# Main.net
KiCad netlist of a schematic drawn in Altium Designer
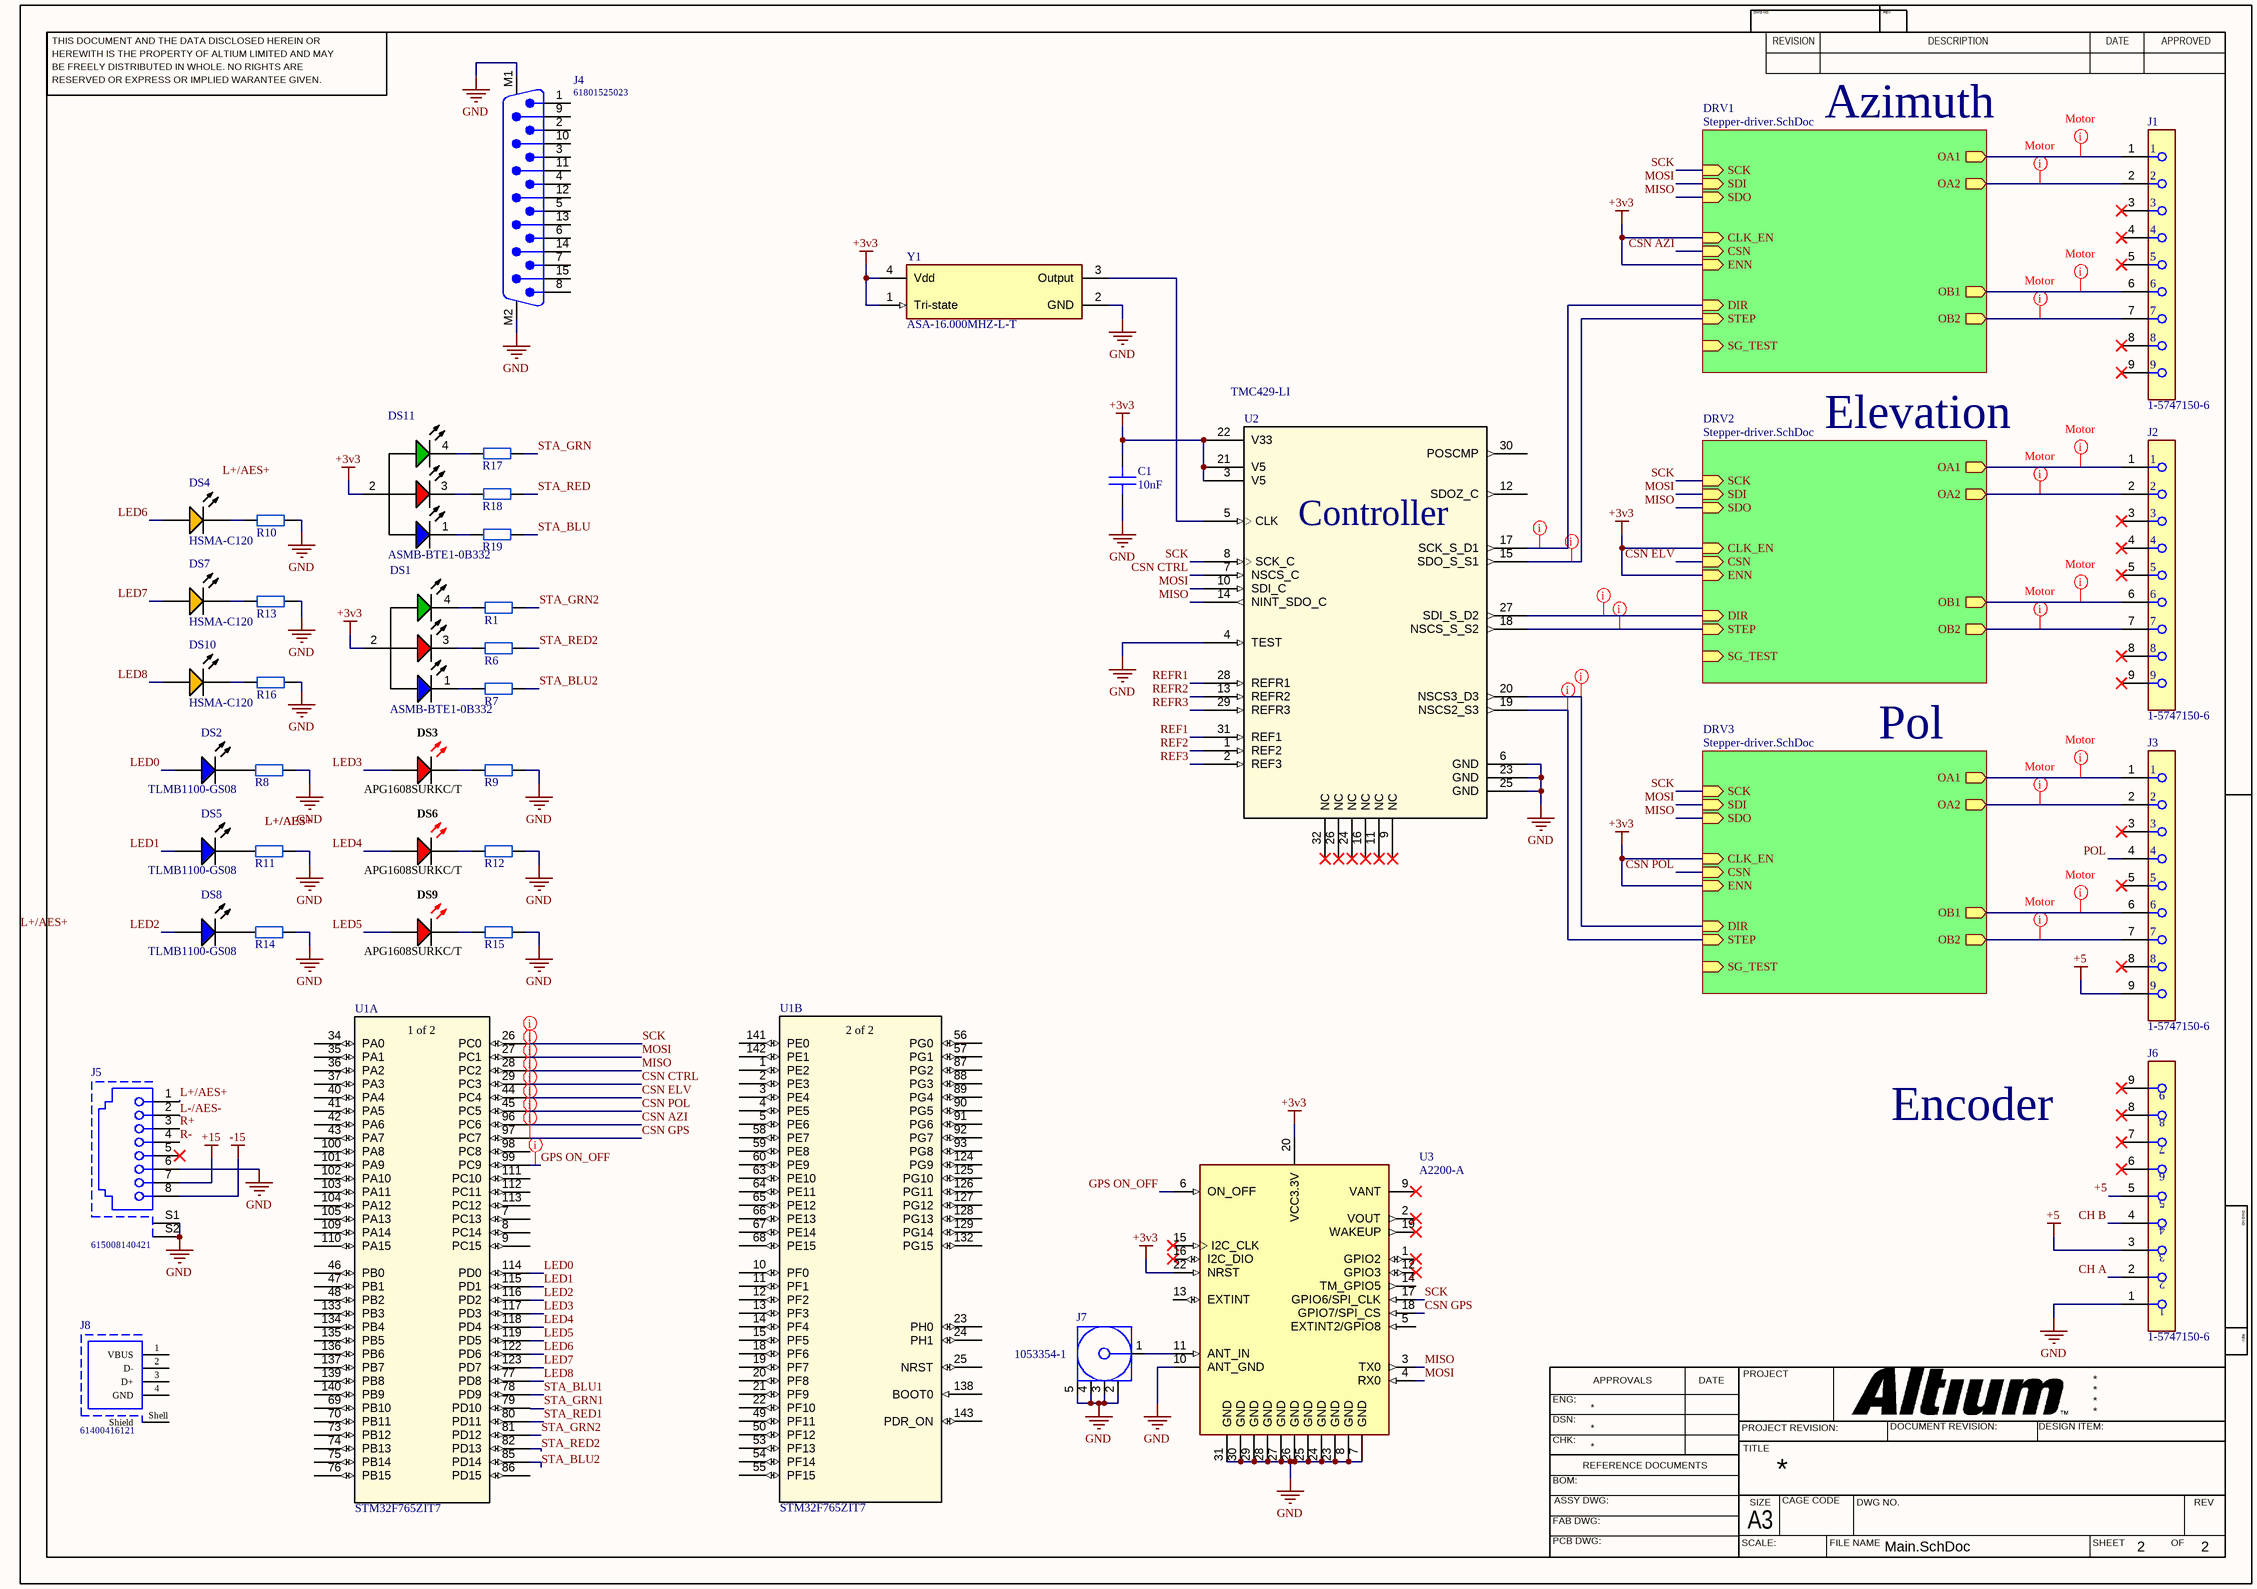
[diagram p0: Main.SchDoc]

(export (version "E")
  (design (tool "Eeschema 10.0.6"))
  (components
    (comp (ref "C1")
      (value "10nF")
      (footprint "C0603 (1608)")
      (fields (field (name "Comment") "Cap SMD"))
      (libsource (lib "Moto Symbol Lib") (part "Cap SMD"))
    )
    (comp (ref "DS1")
      (value "ASMB-BTE1-0B332")
      (footprint "FP-ASMB-BTE1-0B332-MFG")
      (description "LED RGB DIFFUSED 4PLCC SMD")
      (fields
        (field (name "MANUFACTURER") "Broadcom")
        (field (name "OCTOPART") "https://octopart.com/asmb-bte1-0b332-broadcom-71127192")
      )
      (libsource (lib "Moto Symbol Lib") (part "ASMB-BTE1-0B332 RGB LED"))
    )
    (comp (ref "DS2")
      (value "TLMB1100-GS08")
      (footprint "VISH-TLMX1100-2_V")
      (description "Blue LED, 10 mA, 3.9 V, -40 to 100 degC, 2-Pin SMD (0603), RoHS, Tape and Reel")
      (fields (field (name "TOLERANCE") "10%"))
      (libsource (lib "Altium Content Vault") (part "LED-BLUE-AK-2"))
    )
    (comp (ref "DS3")
      (value "APG1608SURKC/T")
      (footprint "KING-LED0603-25-RED_V")
      (fields (field (name "MANUFACTURER") "Kingbright"))
      (libsource (lib "Altium Content Vault") (part "KING-LED_RED_A1K2-2"))
    )
    (comp (ref "DS4")
      (value "HSMA-C120")
      (footprint "AVAG-HSMA-C120-2_V")
      (description "High Performance Chip LED, 1.9 V, -40 to 85 degC, 2-Pin SMD (0603), RoHS, Tape and Reel")
      (fields (field (name "MANUFACTURER") "Avago"))
      (libsource (lib "Altium Content Vault") (part "LED-AMBER-AK-2"))
    )
    (comp (ref "DS5")
      (value "TLMB1100-GS08")
      (footprint "VISH-TLMX1100-2_V")
      (description "Blue LED, 10 mA, 3.9 V, -40 to 100 degC, 2-Pin SMD (0603), RoHS, Tape and Reel")
      (fields (field (name "TOLERANCE") "10%"))
      (libsource (lib "Altium Content Vault") (part "LED-BLUE-AK-2"))
    )
    (comp (ref "DS6")
      (value "APG1608SURKC/T")
      (footprint "KING-LED0603-25-RED_V")
      (fields (field (name "MANUFACTURER") "Kingbright"))
      (libsource (lib "Altium Content Vault") (part "KING-LED_RED_A1K2-2"))
    )
    (comp (ref "DS7")
      (value "HSMA-C120")
      (footprint "AVAG-HSMA-C120-2_V")
      (description "High Performance Chip LED, 1.9 V, -40 to 85 degC, 2-Pin SMD (0603), RoHS, Tape and Reel")
      (fields (field (name "MANUFACTURER") "Avago"))
      (libsource (lib "Altium Content Vault") (part "LED-AMBER-AK-2"))
    )
    (comp (ref "DS8")
      (value "TLMB1100-GS08")
      (footprint "VISH-TLMX1100-2_V")
      (description "Blue LED, 10 mA, 3.9 V, -40 to 100 degC, 2-Pin SMD (0603), RoHS, Tape and Reel")
      (fields (field (name "TOLERANCE") "10%"))
      (libsource (lib "Altium Content Vault") (part "LED-BLUE-AK-2"))
    )
    (comp (ref "DS9")
      (value "APG1608SURKC/T")
      (footprint "KING-LED0603-25-RED_V")
      (fields (field (name "MANUFACTURER") "Kingbright"))
      (libsource (lib "Altium Content Vault") (part "KING-LED_RED_A1K2-2"))
    )
    (comp (ref "DS10")
      (value "HSMA-C120")
      (footprint "AVAG-HSMA-C120-2_V")
      (description "High Performance Chip LED, 1.9 V, -40 to 85 degC, 2-Pin SMD (0603), RoHS, Tape and Reel")
      (fields (field (name "MANUFACTURER") "Avago"))
      (libsource (lib "Altium Content Vault") (part "LED-AMBER-AK-2"))
    )
    (comp (ref "DS11")
      (value "ASMB-BTE1-0B332")
      (footprint "FP-ASMB-BTE1-0B332-MFG")
      (description "LED RGB DIFFUSED 4PLCC SMD")
      (fields
        (field (name "MANUFACTURER") "Broadcom")
        (field (name "OCTOPART") "https://octopart.com/asmb-bte1-0b332-broadcom-71127192")
      )
      (libsource (lib "Moto Symbol Lib") (part "ASMB-BTE1-0B332 RGB LED"))
    )
    (comp (ref "J1")
      (value "1-5747150-6")
      (footprint "FP-1-5747150-6-MFG")
      (description "CONN D-SUB RCPT 9POS VERT SOLDER")
      (fields
        (field (name "OCTOPART") "https://octopart.com/1-5747150-6-te+connectivity-39500344")
        (field (name "MANUFACTURER") "TE Connectivity")
      )
      (libsource (lib "Altium Content Vault") (part "deee9d0d87fff07c08bdfa5b86cd5a5"))
    )
    (comp (ref "J2")
      (value "1-5747150-6")
      (footprint "FP-1-5747150-6-MFG")
      (description "CONN D-SUB RCPT 9POS VERT SOLDER")
      (fields
        (field (name "OCTOPART") "https://octopart.com/1-5747150-6-te+connectivity-39500344")
        (field (name "MANUFACTURER") "TE Connectivity")
      )
      (libsource (lib "Altium Content Vault") (part "deee9d0d87fff07c08bdfa5b86cd5a5"))
    )
    (comp (ref "J3")
      (value "1-5747150-6")
      (footprint "FP-1-5747150-6-MFG")
      (description "CONN D-SUB RCPT 9POS VERT SOLDER")
      (fields
        (field (name "OCTOPART") "https://octopart.com/1-5747150-6-te+connectivity-39500344")
        (field (name "MANUFACTURER") "TE Connectivity")
      )
      (libsource (lib "Altium Content Vault") (part "deee9d0d87fff07c08bdfa5b86cd5a5"))
    )
    (comp (ref "J4")
      (value "61801525023")
      (footprint "61801525023")
      (description "Male PCB Connector WR-DSUB, Vertical, 15 pins")
      (fields (field (name "MANUFACTURER") "Wurth Elektronik") (field (name "PUBLISHER") "WurthElektronik"))
      (libsource (lib "Altium Content Vault") (part "WE-CN-2S-2M-D15"))
    )
    (comp (ref "J5")
      (value "615008140421")
      (footprint "615008140421")
      (description "Modular Jack WR-MJ, Rear Post, Shielded, Vertical Entry, THT, 8P8C")
      (fields (field (name "MANUFACTURER") "Wurth Elektronik") (field (name "PUBLISHER") "WurthElektronik"))
      (libsource (lib "Altium Content Vault") (part "WE-CN-1P-2F-J8"))
    )
    (comp (ref "J6")
      (value "1-5747150-6")
      (footprint "FP-1-5747150-6-MFG")
      (description "CONN D-SUB RCPT 9POS VERT SOLDER")
      (fields
        (field (name "OCTOPART") "https://octopart.com/1-5747150-6-te+connectivity-39500344")
        (field (name "MANUFACTURER") "TE Connectivity")
      )
      (libsource (lib "") (part "deee9d0d87fff07c08bdfa5b86cd5a5_1"))
    )
    (comp (ref "J7")
      (value "1053354-1")
      (footprint "TECO-1053354-1_V")
      (description "Female Coaxial Connector, Pitch 2.55 mm, Height 9.5 mm, Tail Length 3.9 mm, RoHS, Bulk")
      (fields (field (name "MANUFACTURER") "TE Connectivity"))
      (libsource (lib "Altium Content Vault") (part "CN-S-4F-RF5"))
    )
    (comp (ref "J8")
      (value "61400416121")
      (footprint "61400416121")
      (description "USB 2.0 Type B Receptacle WR-COM, Horizontal, THT, with Pads and Pegs")
      (fields (field (name "MANUFACTURER") "Wurth Elektronik") (field (name "PUBLISHER") "WurthElektronik"))
      (libsource (lib "Altium Content Vault") (part "WE-USB-4-1SHLD"))
    )
    (comp (ref "R1")
      (value "Res")
      (footprint "R0603 (1608)")
      (libsource (lib "Moto Symbol Lib") (part "Resistor EU"))
    )
    (comp (ref "R6")
      (value "Res")
      (footprint "R0603 (1608)")
      (libsource (lib "Moto Symbol Lib") (part "Resistor EU"))
    )
    (comp (ref "R7")
      (value "Res")
      (footprint "R0603 (1608)")
      (libsource (lib "Moto Symbol Lib") (part "Resistor EU"))
    )
    (comp (ref "R8")
      (value "Res")
      (footprint "R0603 (1608)")
      (libsource (lib "Moto Symbol Lib") (part "Resistor EU"))
    )
    (comp (ref "R9")
      (value "Res")
      (footprint "R0603 (1608)")
      (libsource (lib "Moto Symbol Lib") (part "Resistor EU"))
    )
    (comp (ref "R10")
      (value "Res")
      (footprint "R0603 (1608)")
      (libsource (lib "Moto Symbol Lib") (part "Resistor EU"))
    )
    (comp (ref "R11")
      (value "Res")
      (footprint "R0603 (1608)")
      (libsource (lib "Moto Symbol Lib") (part "Resistor EU"))
    )
    (comp (ref "R12")
      (value "Res")
      (footprint "R0603 (1608)")
      (libsource (lib "Moto Symbol Lib") (part "Resistor EU"))
    )
    (comp (ref "R13")
      (value "Res")
      (footprint "R0603 (1608)")
      (libsource (lib "Moto Symbol Lib") (part "Resistor EU"))
    )
    (comp (ref "R14")
      (value "Res")
      (footprint "R0603 (1608)")
      (libsource (lib "Moto Symbol Lib") (part "Resistor EU"))
    )
    (comp (ref "R15")
      (value "Res")
      (footprint "R0603 (1608)")
      (libsource (lib "Moto Symbol Lib") (part "Resistor EU"))
    )
    (comp (ref "R16")
      (value "Res")
      (footprint "R0603 (1608)")
      (libsource (lib "Moto Symbol Lib") (part "Resistor EU"))
    )
    (comp (ref "R17")
      (value "Res")
      (footprint "R0603 (1608)")
      (libsource (lib "Moto Symbol Lib") (part "Resistor EU"))
    )
    (comp (ref "R18")
      (value "Res")
      (footprint "R0603 (1608)")
      (libsource (lib "Moto Symbol Lib") (part "Resistor EU"))
    )
    (comp (ref "R19")
      (value "Res")
      (footprint "R0603 (1608)")
      (libsource (lib "Moto Symbol Lib") (part "Resistor EU"))
    )
    (comp (ref "U1")
      (value "STM32F765ZIT7")
      (footprint "LQFP-144_STM-M")
      (description "No Description Available")
      (fields (field (name "COPYRIGHT") "Copyright (C) 2018 Accelerated Designs. All rights reserved"))
      (libsource (lib "Moto Symbol Lib") (part "STM32F765ZIT7"))
    )
    (comp (ref "U2")
      (value "TMC429-LI")
      (footprint "QFN32_5X5_TRI-M")
      (description "No Description Available")
      (fields (field (name "COPYRIGHT") "Copyright (C) 2016 Accelerated Designs. All rights reserved"))
      (libsource (lib "Moto Symbol Lib") (part "TMC429-LI"))
    )
    (comp (ref "U3")
      (value "A2200-A")
      (footprint "SnapEDApcb:XCVR_A2200-A")
      (description "SiRFstarIVâ„¢ RF Receiver GPS 1.575GHz -163dBm 115.2kbps Module")
      (fields (field (name "MF") "Maestro Wireless"))
      (libsource (lib "Moto Symbol Lib") (part "A2200-A"))
    )
    (comp (ref "Y1")
      (value "ASA-16.000MHZ-L-T")
      (footprint "FP-ASA-MFG")
      (description "XTAL OSC XO 16.0000MHZ HCMOS SMD")
      (fields
        (field (name "OCTOPART") "https://octopart.com/asa-16.000mhz-l-t-abracon-21707822")
        (field (name "MANUFACTURER") "Abracon")
      )
      (libsource (lib "Altium Content Vault") (part "7c953fa1d91b086b7cda9813af2bec8"))
    )
  )
  (nets
    (net (code "1") (name "+3v3") (class "Default")
      (node (ref "C1") (pin "2") (pinfunction "2_2") (pintype "power_in"))
      (node (ref "DS1") (pin "2") (pinfunction "Common_Anode_2") (pintype "passive"))
      (node (ref "DS11") (pin "2") (pinfunction "Common_Anode_2") (pintype "passive"))
      (node (ref "U2") (pin "21") (pinfunction "V5_21") (pintype "power_in"))
      (node (ref "U2") (pin "22") (pinfunction "V33_22") (pintype "power_in"))
      (node (ref "U2") (pin "3") (pinfunction "V5_3") (pintype "power_in"))
      (node (ref "U3") (pin "20") (pinfunction "VCC3.3V_20") (pintype "power_in"))
      (node (ref "U3") (pin "22") (pinfunction "NRST_22") (pintype "input"))
      (node (ref "Y1") (pin "1") (pinfunction "Tri-state_1") (pintype "input"))
      (node (ref "Y1") (pin "4") (pinfunction "Vdd_4") (pintype "power_in"))
    )
    (net (code "2") (name "+5") (class "Default")
      (node (ref "J3") (pin "9") (pinfunction "9_9") (pintype "passive"))
      (node (ref "J6") (pin "3") (pinfunction "3_3") (pintype "passive"))
      (node (ref "J6") (pin "5") (pinfunction "5_5") (pintype "passive"))
    )
    (net (code "3") (name "+15") (class "Default")
      (node (ref "J5") (pin "7") (pinfunction "7_7") (pintype "passive"))
    )
    (net (code "4") (name "-15") (class "Default")
      (node (ref "J5") (pin "8") (pinfunction "8_8") (pintype "passive"))
    )
    (net (code "5") (name "/<NO NET>") (class "Default")
      (node (ref "U2") (pin "19") (pinfunction "NSCS2_S3_19") (pintype "output"))
    )
    (net (code "6") (name "/CH A") (class "Default")
      (node (ref "J6") (pin "2") (pinfunction "2_2") (pintype "passive"))
    )
    (net (code "7") (name "/CH B") (class "Default")
      (node (ref "J6") (pin "4") (pinfunction "4_4") (pintype "passive"))
    )
    (net (code "8") (name "/CSN AZI") (class "Default")
      (node (ref "U1") (pin "96") (pinfunction "PC6_96") (pintype "bidirectional"))
    )
    (net (code "9") (name "/CSN CTRL") (class "Default")
      (node (ref "U1") (pin "29") (pinfunction "PC3_29") (pintype "bidirectional"))
      (node (ref "U2") (pin "7") (pinfunction "NSCS_C_7") (pintype "input"))
    )
    (net (code "10") (name "/CSN ELV") (class "Default")
      (node (ref "U1") (pin "44") (pinfunction "PC4_44") (pintype "bidirectional"))
    )
    (net (code "11") (name "/CSN GPS") (class "Default")
      (node (ref "U1") (pin "97") (pinfunction "PC7_97") (pintype "bidirectional"))
      (node (ref "U3") (pin "18") (pinfunction "GPIO7/SPI_CS_18") (pintype "input"))
    )
    (net (code "12") (name "/CSN POL") (class "Default")
      (node (ref "U1") (pin "45") (pinfunction "PC5_45") (pintype "bidirectional"))
    )
    (net (code "13") (name "/DIR") (class "Default")
      (node (ref "U2") (pin "20") (pinfunction "NSCS3_D3_20") (pintype "output"))
    )
    (net (code "14") (name "/DIR_1") (class "Default")
      (node (ref "U2") (pin "17") (pinfunction "SCK_S_D1_17") (pintype "output"))
    )
    (net (code "15") (name "/DIR_2") (class "Default")
      (node (ref "U2") (pin "27") (pinfunction "SDI_S_D2_27") (pintype "output"))
    )
    (net (code "16") (name "/GPS ON_OFF") (class "Default")
      (node (ref "U1") (pin "99") (pinfunction "PC9_99") (pintype "bidirectional"))
      (node (ref "U3") (pin "6") (pinfunction "ON_OFF_6") (pintype "input"))
    )
    (net (code "17") (name "/L+{slash}AES+") (class "Default")
      (node (ref "J5") (pin "1") (pinfunction "1_1") (pintype "passive"))
    )
    (net (code "18") (name "/L-{slash}AES-") (class "Default")
      (node (ref "J5") (pin "2") (pinfunction "2_2") (pintype "passive"))
    )
    (net (code "19") (name "/LED0") (class "Default")
      (node (ref "DS2") (pin "1") (pinfunction "A_1") (pintype "passive"))
      (node (ref "U1") (pin "114") (pinfunction "PD0_114") (pintype "bidirectional"))
    )
    (net (code "20") (name "/LED1") (class "Default")
      (node (ref "DS5") (pin "1") (pinfunction "A_1") (pintype "passive"))
      (node (ref "U1") (pin "115") (pinfunction "PD1_115") (pintype "bidirectional"))
    )
    (net (code "21") (name "/LED2") (class "Default")
      (node (ref "DS8") (pin "1") (pinfunction "A_1") (pintype "passive"))
      (node (ref "U1") (pin "116") (pinfunction "PD2_116") (pintype "bidirectional"))
    )
    (net (code "22") (name "/LED3") (class "Default")
      (node (ref "DS3") (pin "1") (pinfunction "A_1") (pintype "passive"))
      (node (ref "U1") (pin "117") (pinfunction "PD3_117") (pintype "bidirectional"))
    )
    (net (code "23") (name "/LED4") (class "Default")
      (node (ref "DS6") (pin "1") (pinfunction "A_1") (pintype "passive"))
      (node (ref "U1") (pin "118") (pinfunction "PD4_118") (pintype "bidirectional"))
    )
    (net (code "24") (name "/LED5") (class "Default")
      (node (ref "DS9") (pin "1") (pinfunction "A_1") (pintype "passive"))
      (node (ref "U1") (pin "119") (pinfunction "PD5_119") (pintype "bidirectional"))
    )
    (net (code "25") (name "/LED6") (class "Default")
      (node (ref "DS4") (pin "1") (pinfunction "A_1") (pintype "passive"))
      (node (ref "U1") (pin "122") (pinfunction "PD6_122") (pintype "bidirectional"))
    )
    (net (code "26") (name "/LED7") (class "Default")
      (node (ref "DS7") (pin "1") (pinfunction "A_1") (pintype "passive"))
      (node (ref "U1") (pin "123") (pinfunction "PD7_123") (pintype "bidirectional"))
    )
    (net (code "27") (name "/LED8") (class "Default")
      (node (ref "DS10") (pin "1") (pinfunction "A_1") (pintype "passive"))
      (node (ref "U1") (pin "77") (pinfunction "PD8_77") (pintype "bidirectional"))
    )
    (net (code "28") (name "/MISO") (class "Default")
      (node (ref "U1") (pin "28") (pinfunction "PC2_28") (pintype "bidirectional"))
      (node (ref "U2") (pin "14") (pinfunction "NINT_SDO_C_14") (pintype "output"))
      (node (ref "U3") (pin "3") (pinfunction "TX0_3") (pintype "output"))
    )
    (net (code "29") (name "/MOSI") (class "Default")
      (node (ref "U1") (pin "27") (pinfunction "PC1_27") (pintype "bidirectional"))
      (node (ref "U2") (pin "10") (pinfunction "SDI_C_10") (pintype "input"))
      (node (ref "U3") (pin "4") (pinfunction "RX0_4") (pintype "input"))
    )
    (net (code "30") (name "/OA1") (class "Default")
      (node (ref "J3") (pin "1") (pinfunction "1_1") (pintype "passive"))
    )
    (net (code "31") (name "/OA1_1") (class "Default")
      (node (ref "J1") (pin "1") (pinfunction "1_1") (pintype "passive"))
    )
    (net (code "32") (name "/OA1_2") (class "Default")
      (node (ref "J2") (pin "1") (pinfunction "1_1") (pintype "passive"))
    )
    (net (code "33") (name "/OA2") (class "Default")
      (node (ref "J3") (pin "2") (pinfunction "2_2") (pintype "passive"))
    )
    (net (code "34") (name "/OA2_1") (class "Default")
      (node (ref "J1") (pin "2") (pinfunction "2_2") (pintype "passive"))
    )
    (net (code "35") (name "/OA2_2") (class "Default")
      (node (ref "J2") (pin "2") (pinfunction "2_2") (pintype "passive"))
    )
    (net (code "36") (name "/OB1") (class "Default")
      (node (ref "J3") (pin "6") (pinfunction "6_6") (pintype "passive"))
    )
    (net (code "37") (name "/OB1_1") (class "Default")
      (node (ref "J1") (pin "6") (pinfunction "6_6") (pintype "passive"))
    )
    (net (code "38") (name "/OB1_2") (class "Default")
      (node (ref "J2") (pin "6") (pinfunction "6_6") (pintype "passive"))
    )
    (net (code "39") (name "/OB2") (class "Default")
      (node (ref "J3") (pin "7") (pinfunction "7_7") (pintype "passive"))
    )
    (net (code "40") (name "/OB2_1") (class "Default")
      (node (ref "J1") (pin "7") (pinfunction "7_7") (pintype "passive"))
    )
    (net (code "41") (name "/OB2_2") (class "Default")
      (node (ref "J2") (pin "7") (pinfunction "7_7") (pintype "passive"))
    )
    (net (code "42") (name "/POL") (class "Default")
      (node (ref "J3") (pin "4") (pinfunction "4_4") (pintype "passive"))
    )
    (net (code "43") (name "/R+") (class "Default")
      (node (ref "J5") (pin "3") (pinfunction "3_3") (pintype "passive"))
    )
    (net (code "44") (name "/R-") (class "Default")
      (node (ref "J5") (pin "4") (pinfunction "4_4") (pintype "passive"))
    )
    (net (code "45") (name "/REF1") (class "Default")
      (node (ref "U2") (pin "31") (pinfunction "REF1_31") (pintype "input"))
    )
    (net (code "46") (name "/REF2") (class "Default")
      (node (ref "U2") (pin "1") (pinfunction "REF2_1") (pintype "input"))
    )
    (net (code "47") (name "/REF3") (class "Default")
      (node (ref "U2") (pin "2") (pinfunction "REF3_2") (pintype "input"))
    )
    (net (code "48") (name "/REFR1") (class "Default")
      (node (ref "U2") (pin "28") (pinfunction "REFR1_28") (pintype "input"))
    )
    (net (code "49") (name "/REFR2") (class "Default")
      (node (ref "U2") (pin "13") (pinfunction "REFR2_13") (pintype "input"))
    )
    (net (code "50") (name "/REFR3") (class "Default")
      (node (ref "U2") (pin "29") (pinfunction "REFR3_29") (pintype "input"))
    )
    (net (code "51") (name "/SCK") (class "Default")
      (node (ref "U1") (pin "26") (pinfunction "PC0_26") (pintype "bidirectional"))
      (node (ref "U2") (pin "8") (pinfunction "SCK_C_8") (pintype "input"))
      (node (ref "U3") (pin "17") (pinfunction "GPIO6/SPI_CLK_17") (pintype "input"))
    )
    (net (code "55") (name "/STA_BLU") (class "Default")
      (node (ref "R19") (pin "2") (pinfunction "2_2") (pintype "power_in"))
    )
    (net (code "56") (name "/STA_BLU1") (class "Default")
      (node (ref "U1") (pin "78") (pinfunction "PD9_78") (pintype "bidirectional"))
    )
    (net (code "57") (name "/STA_BLU2") (class "Default")
      (node (ref "R7") (pin "2") (pinfunction "2_2") (pintype "power_in"))
      (node (ref "U1") (pin "85") (pinfunction "PD14_85") (pintype "bidirectional"))
    )
    (net (code "58") (name "/STA_GRN") (class "Default")
      (node (ref "R17") (pin "2") (pinfunction "2_2") (pintype "power_in"))
    )
    (net (code "60") (name "/STA_GRN2") (class "Default")
      (node (ref "R1") (pin "2") (pinfunction "2_2") (pintype "power_in"))
      (node (ref "U1") (pin "81") (pinfunction "PD12_81") (pintype "bidirectional"))
    )
    (net (code "61") (name "/STA_RED") (class "Default")
      (node (ref "R18") (pin "2") (pinfunction "2_2") (pintype "power_in"))
    )
    (net (code "62") (name "/STA_RED1") (class "Default")
      (node (ref "U1") (pin "80") (pinfunction "PD11_80") (pintype "bidirectional"))
    )
    (net (code "63") (name "/STA_RED2") (class "Default")
      (node (ref "R6") (pin "2") (pinfunction "2_2") (pintype "power_in"))
      (node (ref "U1") (pin "82") (pinfunction "PD13_82") (pintype "bidirectional"))
    )
    (net (code "64") (name "/STEP") (class "Default")
      (node (ref "U2") (pin "18") (pinfunction "NSCS_S_S2_18") (pintype "output"))
    )
    (net (code "65") (name "/STEP_1") (class "Default")
      (node (ref "U2") (pin "15") (pinfunction "SDO_S_S1_15") (pintype "output"))
    )
    (net (code "66") (name "GND") (class "Default")
      (node (ref "C1") (pin "1") (pinfunction "1_1") (pintype "power_in"))
      (node (ref "J4") (pin "M1") (pinfunction "M1_M1") (pintype "passive"))
      (node (ref "J4") (pin "M2") (pinfunction "M2_M2") (pintype "passive"))
      (node (ref "J5") (pin "6") (pinfunction "6_6") (pintype "passive"))
      (node (ref "J5") (pin "S1") (pinfunction "S1_S1") (pintype "passive"))
      (node (ref "J5") (pin "S2") (pinfunction "S2_S2") (pintype "passive"))
      (node (ref "J6") (pin "1") (pinfunction "1_1") (pintype "passive"))
      (node (ref "J7") (pin "2") (pinfunction "2_2") (pintype "passive"))
      (node (ref "J7") (pin "3") (pinfunction "3_3") (pintype "passive"))
      (node (ref "J7") (pin "4") (pinfunction "4_4") (pintype "passive"))
      (node (ref "J7") (pin "5") (pinfunction "5_5") (pintype "passive"))
      (node (ref "R10") (pin "2") (pinfunction "2_2") (pintype "power_in"))
      (node (ref "R11") (pin "2") (pinfunction "2_2") (pintype "power_in"))
      (node (ref "R12") (pin "2") (pinfunction "2_2") (pintype "power_in"))
      (node (ref "R13") (pin "2") (pinfunction "2_2") (pintype "power_in"))
      (node (ref "R14") (pin "2") (pinfunction "2_2") (pintype "power_in"))
      (node (ref "R15") (pin "2") (pinfunction "2_2") (pintype "power_in"))
      (node (ref "R16") (pin "2") (pinfunction "2_2") (pintype "power_in"))
      (node (ref "R8") (pin "2") (pinfunction "2_2") (pintype "power_in"))
      (node (ref "R9") (pin "2") (pinfunction "2_2") (pintype "power_in"))
      (node (ref "U2") (pin "23") (pinfunction "GND_23") (pintype "power_in"))
      (node (ref "U2") (pin "25") (pinfunction "GND_25") (pintype "power_in"))
      (node (ref "U2") (pin "4") (pinfunction "TEST_4") (pintype "input"))
      (node (ref "U2") (pin "6") (pinfunction "GND_6") (pintype "power_in"))
      (node (ref "U3") (pin "10") (pinfunction "ANT_GND_10") (pintype "power_in"))
      (node (ref "U3") (pin "23") (pinfunction "GND_23") (pintype "power_in"))
      (node (ref "U3") (pin "24") (pinfunction "GND_24") (pintype "power_in"))
      (node (ref "U3") (pin "25") (pinfunction "GND_25") (pintype "power_in"))
      (node (ref "U3") (pin "26") (pinfunction "GND_26") (pintype "power_in"))
      (node (ref "U3") (pin "27") (pinfunction "GND_27") (pintype "power_in"))
      (node (ref "U3") (pin "28") (pinfunction "GND_28") (pintype "power_in"))
      (node (ref "U3") (pin "29") (pinfunction "GND_29") (pintype "power_in"))
      (node (ref "U3") (pin "30") (pinfunction "GND_30") (pintype "power_in"))
      (node (ref "U3") (pin "31") (pinfunction "GND_31") (pintype "power_in"))
      (node (ref "U3") (pin "7") (pinfunction "GND_7") (pintype "power_in"))
      (node (ref "U3") (pin "8") (pinfunction "GND_8") (pintype "power_in"))
      (node (ref "Y1") (pin "2") (pinfunction "GND_2") (pintype "power_in"))
    )
    (net (code "67") (name "Net-(DS1-Cathode(Blue))") (class "Default")
      (node (ref "DS1") (pin "1") (pinfunction "Cathode(Blue)_1") (pintype "passive"))
      (node (ref "R7") (pin "1") (pinfunction "1_1") (pintype "power_in"))
    )
    (net (code "68") (name "Net-(DS1-Cathode(Green))") (class "Default")
      (node (ref "DS1") (pin "4") (pinfunction "Cathode(Green)_4") (pintype "passive"))
      (node (ref "R1") (pin "1") (pinfunction "1_1") (pintype "power_in"))
    )
    (net (code "69") (name "Net-(DS1-Cathode(Red))") (class "Default")
      (node (ref "DS1") (pin "3") (pinfunction "Cathode(Red)_3") (pintype "passive"))
      (node (ref "R6") (pin "1") (pinfunction "1_1") (pintype "power_in"))
    )
    (net (code "70") (name "Net-(DS2-K)") (class "Default")
      (node (ref "DS2") (pin "2") (pinfunction "K_2") (pintype "passive"))
      (node (ref "R8") (pin "1") (pinfunction "1_1") (pintype "power_in"))
    )
    (net (code "71") (name "Net-(DS3-K)") (class "Default")
      (node (ref "DS3") (pin "2") (pinfunction "K_2") (pintype "passive"))
      (node (ref "R9") (pin "1") (pinfunction "1_1") (pintype "power_in"))
    )
    (net (code "72") (name "Net-(DS4-K)") (class "Default")
      (node (ref "DS4") (pin "2") (pinfunction "K_2") (pintype "passive"))
      (node (ref "R10") (pin "1") (pinfunction "1_1") (pintype "power_in"))
    )
    (net (code "73") (name "Net-(DS5-K)") (class "Default")
      (node (ref "DS5") (pin "2") (pinfunction "K_2") (pintype "passive"))
      (node (ref "R11") (pin "1") (pinfunction "1_1") (pintype "power_in"))
    )
    (net (code "74") (name "Net-(DS6-K)") (class "Default")
      (node (ref "DS6") (pin "2") (pinfunction "K_2") (pintype "passive"))
      (node (ref "R12") (pin "1") (pinfunction "1_1") (pintype "power_in"))
    )
    (net (code "75") (name "Net-(DS7-K)") (class "Default")
      (node (ref "DS7") (pin "2") (pinfunction "K_2") (pintype "passive"))
      (node (ref "R13") (pin "1") (pinfunction "1_1") (pintype "power_in"))
    )
    (net (code "76") (name "Net-(DS8-K)") (class "Default")
      (node (ref "DS8") (pin "2") (pinfunction "K_2") (pintype "passive"))
      (node (ref "R14") (pin "1") (pinfunction "1_1") (pintype "power_in"))
    )
    (net (code "77") (name "Net-(DS9-K)") (class "Default")
      (node (ref "DS9") (pin "2") (pinfunction "K_2") (pintype "passive"))
      (node (ref "R15") (pin "1") (pinfunction "1_1") (pintype "power_in"))
    )
    (net (code "78") (name "Net-(DS10-K)") (class "Default")
      (node (ref "DS10") (pin "2") (pinfunction "K_2") (pintype "passive"))
      (node (ref "R16") (pin "1") (pinfunction "1_1") (pintype "power_in"))
    )
    (net (code "79") (name "Net-(DS11-Cathode(Blue))") (class "Default")
      (node (ref "DS11") (pin "1") (pinfunction "Cathode(Blue)_1") (pintype "passive"))
      (node (ref "R19") (pin "1") (pinfunction "1_1") (pintype "power_in"))
    )
    (net (code "80") (name "Net-(DS11-Cathode(Green))") (class "Default")
      (node (ref "DS11") (pin "4") (pinfunction "Cathode(Green)_4") (pintype "passive"))
      (node (ref "R17") (pin "1") (pinfunction "1_1") (pintype "power_in"))
    )
    (net (code "81") (name "Net-(DS11-Cathode(Red))") (class "Default")
      (node (ref "DS11") (pin "3") (pinfunction "Cathode(Red)_3") (pintype "passive"))
      (node (ref "R18") (pin "1") (pinfunction "1_1") (pintype "power_in"))
    )
    (net (code "82") (name "Net-(U2-CLK)") (class "Default")
      (node (ref "U2") (pin "5") (pinfunction "CLK_5") (pintype "input"))
      (node (ref "Y1") (pin "3") (pinfunction "Output_3") (pintype "passive"))
    )
    (net (code "83") (name "Net-(U3-ANT_IN)") (class "Default")
      (node (ref "J7") (pin "1") (pinfunction "1_1") (pintype "passive"))
      (node (ref "U3") (pin "11") (pinfunction "ANT_IN_11") (pintype "input"))
    )
    (net (code "84") (name "unconnected-(J1-Pad3)") (class "Default")
      (node (ref "J1") (pin "3") (pinfunction "3_3") (pintype "passive+no_connect"))
    )
    (net (code "85") (name "unconnected-(J1-Pad4)") (class "Default")
      (node (ref "J1") (pin "4") (pinfunction "4_4") (pintype "passive+no_connect"))
    )
    (net (code "86") (name "unconnected-(J1-Pad5)") (class "Default")
      (node (ref "J1") (pin "5") (pinfunction "5_5") (pintype "passive+no_connect"))
    )
    (net (code "87") (name "unconnected-(J1-Pad8)") (class "Default")
      (node (ref "J1") (pin "8") (pinfunction "8_8") (pintype "passive+no_connect"))
    )
    (net (code "88") (name "unconnected-(J1-Pad9)") (class "Default")
      (node (ref "J1") (pin "9") (pinfunction "9_9") (pintype "passive+no_connect"))
    )
    (net (code "89") (name "unconnected-(J2-Pad3)") (class "Default")
      (node (ref "J2") (pin "3") (pinfunction "3_3") (pintype "passive+no_connect"))
    )
    (net (code "90") (name "unconnected-(J2-Pad4)") (class "Default")
      (node (ref "J2") (pin "4") (pinfunction "4_4") (pintype "passive+no_connect"))
    )
    (net (code "91") (name "unconnected-(J2-Pad5)") (class "Default")
      (node (ref "J2") (pin "5") (pinfunction "5_5") (pintype "passive+no_connect"))
    )
    (net (code "92") (name "unconnected-(J2-Pad8)") (class "Default")
      (node (ref "J2") (pin "8") (pinfunction "8_8") (pintype "passive+no_connect"))
    )
    (net (code "93") (name "unconnected-(J2-Pad9)") (class "Default")
      (node (ref "J2") (pin "9") (pinfunction "9_9") (pintype "passive+no_connect"))
    )
    (net (code "94") (name "unconnected-(J3-Pad3)") (class "Default")
      (node (ref "J3") (pin "3") (pinfunction "3_3") (pintype "passive+no_connect"))
    )
    (net (code "95") (name "unconnected-(J3-Pad5)") (class "Default")
      (node (ref "J3") (pin "5") (pinfunction "5_5") (pintype "passive+no_connect"))
    )
    (net (code "96") (name "unconnected-(J3-Pad8)") (class "Default")
      (node (ref "J3") (pin "8") (pinfunction "8_8") (pintype "passive+no_connect"))
    )
    (net (code "97") (name "unconnected-(J4-Pad1)") (class "Default")
      (node (ref "J4") (pin "1") (pinfunction "1_1") (pintype "passive"))
    )
    (net (code "98") (name "unconnected-(J4-Pad2)") (class "Default")
      (node (ref "J4") (pin "2") (pinfunction "2_2") (pintype "passive"))
    )
    (net (code "99") (name "unconnected-(J4-Pad3)") (class "Default")
      (node (ref "J4") (pin "3") (pinfunction "3_3") (pintype "passive"))
    )
    (net (code "100") (name "unconnected-(J4-Pad4)") (class "Default")
      (node (ref "J4") (pin "4") (pinfunction "4_4") (pintype "passive"))
    )
    (net (code "101") (name "unconnected-(J4-Pad5)") (class "Default")
      (node (ref "J4") (pin "5") (pinfunction "5_5") (pintype "passive"))
    )
    (net (code "102") (name "unconnected-(J4-Pad6)") (class "Default")
      (node (ref "J4") (pin "6") (pinfunction "6_6") (pintype "passive"))
    )
    (net (code "103") (name "unconnected-(J4-Pad7)") (class "Default")
      (node (ref "J4") (pin "7") (pinfunction "7_7") (pintype "passive"))
    )
    (net (code "104") (name "unconnected-(J4-Pad8)") (class "Default")
      (node (ref "J4") (pin "8") (pinfunction "8_8") (pintype "passive"))
    )
    (net (code "105") (name "unconnected-(J4-Pad9)") (class "Default")
      (node (ref "J4") (pin "9") (pinfunction "9_9") (pintype "passive"))
    )
    (net (code "106") (name "unconnected-(J4-Pad10)") (class "Default")
      (node (ref "J4") (pin "10") (pinfunction "10_10") (pintype "passive"))
    )
    (net (code "107") (name "unconnected-(J4-Pad11)") (class "Default")
      (node (ref "J4") (pin "11") (pinfunction "11_11") (pintype "passive"))
    )
    (net (code "108") (name "unconnected-(J4-Pad12)") (class "Default")
      (node (ref "J4") (pin "12") (pinfunction "12_12") (pintype "passive"))
    )
    (net (code "109") (name "unconnected-(J4-Pad13)") (class "Default")
      (node (ref "J4") (pin "13") (pinfunction "13_13") (pintype "passive"))
    )
    (net (code "110") (name "unconnected-(J4-Pad14)") (class "Default")
      (node (ref "J4") (pin "14") (pinfunction "14_14") (pintype "passive"))
    )
    (net (code "111") (name "unconnected-(J4-Pad15)") (class "Default")
      (node (ref "J4") (pin "15") (pinfunction "15_15") (pintype "passive"))
    )
    (net (code "112") (name "unconnected-(J5-Pad5)") (class "Default")
      (node (ref "J5") (pin "5") (pinfunction "5_5") (pintype "passive+no_connect"))
    )
    (net (code "113") (name "unconnected-(J6-Pad6)") (class "Default")
      (node (ref "J6") (pin "6") (pinfunction "6_6") (pintype "passive+no_connect"))
    )
    (net (code "114") (name "unconnected-(J6-Pad7)") (class "Default")
      (node (ref "J6") (pin "7") (pinfunction "7_7") (pintype "passive+no_connect"))
    )
    (net (code "115") (name "unconnected-(J6-Pad8)") (class "Default")
      (node (ref "J6") (pin "8") (pinfunction "8_8") (pintype "passive+no_connect"))
    )
    (net (code "116") (name "unconnected-(J6-Pad9)") (class "Default")
      (node (ref "J6") (pin "9") (pinfunction "9_9") (pintype "passive+no_connect"))
    )
    (net (code "117") (name "unconnected-(J8-D+-Pad3)") (class "Default")
      (node (ref "J8") (pin "3") (pinfunction "D+_3") (pintype "passive"))
    )
    (net (code "118") (name "unconnected-(J8-D--Pad2)") (class "Default")
      (node (ref "J8") (pin "2") (pinfunction "D-_2") (pintype "passive"))
    )
    (net (code "119") (name "unconnected-(J8-GND-Pad4)") (class "Default")
      (node (ref "J8") (pin "4") (pinfunction "GND_4") (pintype "passive"))
    )
    (net (code "120") (name "unconnected-(J8-Shield-PadShell)") (class "Default")
      (node (ref "J8") (pin "Shell") (pinfunction "Shield_Shell") (pintype "passive"))
    )
    (net (code "121") (name "unconnected-(J8-VBUS-Pad1)") (class "Default")
      (node (ref "J8") (pin "1") (pinfunction "VBUS_1") (pintype "passive"))
    )
    (net (code "122") (name "unconnected-(U1A-PA0-Pad34)") (class "Default")
      (node (ref "U1") (pin "34") (pinfunction "PA0_34") (pintype "bidirectional"))
    )
    (net (code "123") (name "unconnected-(U1A-PA1-Pad35)") (class "Default")
      (node (ref "U1") (pin "35") (pinfunction "PA1_35") (pintype "bidirectional"))
    )
    (net (code "124") (name "unconnected-(U1A-PA2-Pad36)") (class "Default")
      (node (ref "U1") (pin "36") (pinfunction "PA2_36") (pintype "bidirectional"))
    )
    (net (code "125") (name "unconnected-(U1A-PA3-Pad37)") (class "Default")
      (node (ref "U1") (pin "37") (pinfunction "PA3_37") (pintype "bidirectional"))
    )
    (net (code "126") (name "unconnected-(U1A-PA4-Pad40)") (class "Default")
      (node (ref "U1") (pin "40") (pinfunction "PA4_40") (pintype "bidirectional"))
    )
    (net (code "127") (name "unconnected-(U1A-PA5-Pad41)") (class "Default")
      (node (ref "U1") (pin "41") (pinfunction "PA5_41") (pintype "bidirectional"))
    )
    (net (code "128") (name "unconnected-(U1A-PA6-Pad42)") (class "Default")
      (node (ref "U1") (pin "42") (pinfunction "PA6_42") (pintype "bidirectional"))
    )
    (net (code "129") (name "unconnected-(U1A-PA7-Pad43)") (class "Default")
      (node (ref "U1") (pin "43") (pinfunction "PA7_43") (pintype "bidirectional"))
    )
    (net (code "130") (name "unconnected-(U1A-PA8-Pad100)") (class "Default")
      (node (ref "U1") (pin "100") (pinfunction "PA8_100") (pintype "bidirectional"))
    )
    (net (code "131") (name "unconnected-(U1A-PA9-Pad101)") (class "Default")
      (node (ref "U1") (pin "101") (pinfunction "PA9_101") (pintype "bidirectional"))
    )
    (net (code "132") (name "unconnected-(U1A-PA10-Pad102)") (class "Default")
      (node (ref "U1") (pin "102") (pinfunction "PA10_102") (pintype "bidirectional"))
    )
    (net (code "133") (name "unconnected-(U1A-PA11-Pad103)") (class "Default")
      (node (ref "U1") (pin "103") (pinfunction "PA11_103") (pintype "bidirectional"))
    )
    (net (code "134") (name "unconnected-(U1A-PA12-Pad104)") (class "Default")
      (node (ref "U1") (pin "104") (pinfunction "PA12_104") (pintype "bidirectional"))
    )
    (net (code "135") (name "unconnected-(U1A-PA13-Pad105)") (class "Default")
      (node (ref "U1") (pin "105") (pinfunction "PA13_105") (pintype "bidirectional"))
    )
    (net (code "136") (name "unconnected-(U1A-PA14-Pad109)") (class "Default")
      (node (ref "U1") (pin "109") (pinfunction "PA14_109") (pintype "bidirectional"))
    )
    (net (code "137") (name "unconnected-(U1A-PA15-Pad110)") (class "Default")
      (node (ref "U1") (pin "110") (pinfunction "PA15_110") (pintype "bidirectional"))
    )
    (net (code "138") (name "unconnected-(U1A-PB0-Pad46)") (class "Default")
      (node (ref "U1") (pin "46") (pinfunction "PB0_46") (pintype "bidirectional"))
    )
    (net (code "139") (name "unconnected-(U1A-PB1-Pad47)") (class "Default")
      (node (ref "U1") (pin "47") (pinfunction "PB1_47") (pintype "bidirectional"))
    )
    (net (code "140") (name "unconnected-(U1A-PB2-Pad48)") (class "Default")
      (node (ref "U1") (pin "48") (pinfunction "PB2_48") (pintype "bidirectional"))
    )
    (net (code "141") (name "unconnected-(U1A-PB3-Pad133)") (class "Default")
      (node (ref "U1") (pin "133") (pinfunction "PB3_133") (pintype "bidirectional"))
    )
    (net (code "142") (name "unconnected-(U1A-PB4-Pad134)") (class "Default")
      (node (ref "U1") (pin "134") (pinfunction "PB4_134") (pintype "bidirectional"))
    )
    (net (code "143") (name "unconnected-(U1A-PB5-Pad135)") (class "Default")
      (node (ref "U1") (pin "135") (pinfunction "PB5_135") (pintype "bidirectional"))
    )
    (net (code "144") (name "unconnected-(U1A-PB6-Pad136)") (class "Default")
      (node (ref "U1") (pin "136") (pinfunction "PB6_136") (pintype "bidirectional"))
    )
    (net (code "145") (name "unconnected-(U1A-PB7-Pad137)") (class "Default")
      (node (ref "U1") (pin "137") (pinfunction "PB7_137") (pintype "bidirectional"))
    )
    (net (code "146") (name "unconnected-(U1A-PB8-Pad139)") (class "Default")
      (node (ref "U1") (pin "139") (pinfunction "PB8_139") (pintype "bidirectional"))
    )
    (net (code "147") (name "unconnected-(U1A-PB9-Pad140)") (class "Default")
      (node (ref "U1") (pin "140") (pinfunction "PB9_140") (pintype "bidirectional"))
    )
    (net (code "148") (name "unconnected-(U1A-PB10-Pad69)") (class "Default")
      (node (ref "U1") (pin "69") (pinfunction "PB10_69") (pintype "bidirectional"))
    )
    (net (code "149") (name "unconnected-(U1A-PB11-Pad70)") (class "Default")
      (node (ref "U1") (pin "70") (pinfunction "PB11_70") (pintype "bidirectional"))
    )
    (net (code "150") (name "unconnected-(U1A-PB12-Pad73)") (class "Default")
      (node (ref "U1") (pin "73") (pinfunction "PB12_73") (pintype "bidirectional"))
    )
    (net (code "151") (name "unconnected-(U1A-PB13-Pad74)") (class "Default")
      (node (ref "U1") (pin "74") (pinfunction "PB13_74") (pintype "bidirectional"))
    )
    (net (code "152") (name "unconnected-(U1A-PB14-Pad75)") (class "Default")
      (node (ref "U1") (pin "75") (pinfunction "PB14_75") (pintype "bidirectional"))
    )
    (net (code "153") (name "unconnected-(U1A-PB15-Pad76)") (class "Default")
      (node (ref "U1") (pin "76") (pinfunction "PB15_76") (pintype "bidirectional"))
    )
    (net (code "154") (name "unconnected-(U1A-PC8-Pad98)") (class "Default")
      (node (ref "U1") (pin "98") (pinfunction "PC8_98") (pintype "bidirectional"))
    )
    (net (code "155") (name "unconnected-(U1A-PC10-Pad111)") (class "Default")
      (node (ref "U1") (pin "111") (pinfunction "PC10_111") (pintype "bidirectional"))
    )
    (net (code "156") (name "unconnected-(U1A-PC11-Pad112)") (class "Default")
      (node (ref "U1") (pin "112") (pinfunction "PC11_112") (pintype "bidirectional"))
    )
    (net (code "157") (name "unconnected-(U1A-PC12-Pad113)") (class "Default")
      (node (ref "U1") (pin "113") (pinfunction "PC12_113") (pintype "bidirectional"))
    )
    (net (code "158") (name "unconnected-(U1A-PC13-Pad7)") (class "Default")
      (node (ref "U1") (pin "7") (pinfunction "PC13_7") (pintype "bidirectional"))
    )
    (net (code "159") (name "unconnected-(U1A-PC14-Pad8)") (class "Default")
      (node (ref "U1") (pin "8") (pinfunction "PC14_8") (pintype "bidirectional"))
    )
    (net (code "160") (name "unconnected-(U1A-PC15-Pad9)") (class "Default")
      (node (ref "U1") (pin "9") (pinfunction "PC15_9") (pintype "bidirectional"))
    )
    (net (code "161") (name "unconnected-(U1A-PD10-Pad79)") (class "Default")
      (node (ref "U1") (pin "79") (pinfunction "PD10_79") (pintype "bidirectional"))
    )
    (net (code "162") (name "unconnected-(U1A-PD15-Pad86)") (class "Default")
      (node (ref "U1") (pin "86") (pinfunction "PD15_86") (pintype "bidirectional"))
    )
    (net (code "163") (name "unconnected-(U1B-BOOT0-Pad138)") (class "Default")
      (node (ref "U1") (pin "138") (pinfunction "BOOT0_138") (pintype "input"))
    )
    (net (code "164") (name "unconnected-(U1B-NRST-Pad25)") (class "Default")
      (node (ref "U1") (pin "25") (pinfunction "NRST_25") (pintype "bidirectional"))
    )
    (net (code "165") (name "unconnected-(U1B-PDR_ON-Pad143)") (class "Default")
      (node (ref "U1") (pin "143") (pinfunction "PDR_ON_143") (pintype "bidirectional"))
    )
    (net (code "166") (name "unconnected-(U1B-PE0-Pad141)") (class "Default")
      (node (ref "U1") (pin "141") (pinfunction "PE0_141") (pintype "bidirectional"))
    )
    (net (code "167") (name "unconnected-(U1B-PE1-Pad142)") (class "Default")
      (node (ref "U1") (pin "142") (pinfunction "PE1_142") (pintype "bidirectional"))
    )
    (net (code "168") (name "unconnected-(U1B-PE2-Pad1)") (class "Default")
      (node (ref "U1") (pin "1") (pinfunction "PE2_1") (pintype "bidirectional"))
    )
    (net (code "169") (name "unconnected-(U1B-PE3-Pad2)") (class "Default")
      (node (ref "U1") (pin "2") (pinfunction "PE3_2") (pintype "bidirectional"))
    )
    (net (code "170") (name "unconnected-(U1B-PE4-Pad3)") (class "Default")
      (node (ref "U1") (pin "3") (pinfunction "PE4_3") (pintype "bidirectional"))
    )
    (net (code "171") (name "unconnected-(U1B-PE5-Pad4)") (class "Default")
      (node (ref "U1") (pin "4") (pinfunction "PE5_4") (pintype "bidirectional"))
    )
    (net (code "172") (name "unconnected-(U1B-PE6-Pad5)") (class "Default")
      (node (ref "U1") (pin "5") (pinfunction "PE6_5") (pintype "bidirectional"))
    )
    (net (code "173") (name "unconnected-(U1B-PE7-Pad58)") (class "Default")
      (node (ref "U1") (pin "58") (pinfunction "PE7_58") (pintype "bidirectional"))
    )
    (net (code "174") (name "unconnected-(U1B-PE8-Pad59)") (class "Default")
      (node (ref "U1") (pin "59") (pinfunction "PE8_59") (pintype "bidirectional"))
    )
    (net (code "175") (name "unconnected-(U1B-PE9-Pad60)") (class "Default")
      (node (ref "U1") (pin "60") (pinfunction "PE9_60") (pintype "bidirectional"))
    )
    (net (code "176") (name "unconnected-(U1B-PE10-Pad63)") (class "Default")
      (node (ref "U1") (pin "63") (pinfunction "PE10_63") (pintype "bidirectional"))
    )
    (net (code "177") (name "unconnected-(U1B-PE11-Pad64)") (class "Default")
      (node (ref "U1") (pin "64") (pinfunction "PE11_64") (pintype "bidirectional"))
    )
    (net (code "178") (name "unconnected-(U1B-PE12-Pad65)") (class "Default")
      (node (ref "U1") (pin "65") (pinfunction "PE12_65") (pintype "bidirectional"))
    )
    (net (code "179") (name "unconnected-(U1B-PE13-Pad66)") (class "Default")
      (node (ref "U1") (pin "66") (pinfunction "PE13_66") (pintype "bidirectional"))
    )
    (net (code "180") (name "unconnected-(U1B-PE14-Pad67)") (class "Default")
      (node (ref "U1") (pin "67") (pinfunction "PE14_67") (pintype "bidirectional"))
    )
    (net (code "181") (name "unconnected-(U1B-PE15-Pad68)") (class "Default")
      (node (ref "U1") (pin "68") (pinfunction "PE15_68") (pintype "bidirectional"))
    )
    (net (code "182") (name "unconnected-(U1B-PF0-Pad10)") (class "Default")
      (node (ref "U1") (pin "10") (pinfunction "PF0_10") (pintype "bidirectional"))
    )
    (net (code "183") (name "unconnected-(U1B-PF1-Pad11)") (class "Default")
      (node (ref "U1") (pin "11") (pinfunction "PF1_11") (pintype "bidirectional"))
    )
    (net (code "184") (name "unconnected-(U1B-PF2-Pad12)") (class "Default")
      (node (ref "U1") (pin "12") (pinfunction "PF2_12") (pintype "bidirectional"))
    )
    (net (code "185") (name "unconnected-(U1B-PF3-Pad13)") (class "Default")
      (node (ref "U1") (pin "13") (pinfunction "PF3_13") (pintype "bidirectional"))
    )
    (net (code "186") (name "unconnected-(U1B-PF4-Pad14)") (class "Default")
      (node (ref "U1") (pin "14") (pinfunction "PF4_14") (pintype "bidirectional"))
    )
    (net (code "187") (name "unconnected-(U1B-PF5-Pad15)") (class "Default")
      (node (ref "U1") (pin "15") (pinfunction "PF5_15") (pintype "bidirectional"))
    )
    (net (code "188") (name "unconnected-(U1B-PF6-Pad18)") (class "Default")
      (node (ref "U1") (pin "18") (pinfunction "PF6_18") (pintype "bidirectional"))
    )
    (net (code "189") (name "unconnected-(U1B-PF7-Pad19)") (class "Default")
      (node (ref "U1") (pin "19") (pinfunction "PF7_19") (pintype "bidirectional"))
    )
    (net (code "190") (name "unconnected-(U1B-PF8-Pad20)") (class "Default")
      (node (ref "U1") (pin "20") (pinfunction "PF8_20") (pintype "bidirectional"))
    )
    (net (code "191") (name "unconnected-(U1B-PF9-Pad21)") (class "Default")
      (node (ref "U1") (pin "21") (pinfunction "PF9_21") (pintype "bidirectional"))
    )
    (net (code "192") (name "unconnected-(U1B-PF10-Pad22)") (class "Default")
      (node (ref "U1") (pin "22") (pinfunction "PF10_22") (pintype "bidirectional"))
    )
    (net (code "193") (name "unconnected-(U1B-PF11-Pad49)") (class "Default")
      (node (ref "U1") (pin "49") (pinfunction "PF11_49") (pintype "bidirectional"))
    )
    (net (code "194") (name "unconnected-(U1B-PF12-Pad50)") (class "Default")
      (node (ref "U1") (pin "50") (pinfunction "PF12_50") (pintype "bidirectional"))
    )
    (net (code "195") (name "unconnected-(U1B-PF13-Pad53)") (class "Default")
      (node (ref "U1") (pin "53") (pinfunction "PF13_53") (pintype "bidirectional"))
    )
    (net (code "196") (name "unconnected-(U1B-PF14-Pad54)") (class "Default")
      (node (ref "U1") (pin "54") (pinfunction "PF14_54") (pintype "bidirectional"))
    )
    (net (code "197") (name "unconnected-(U1B-PF15-Pad55)") (class "Default")
      (node (ref "U1") (pin "55") (pinfunction "PF15_55") (pintype "bidirectional"))
    )
    (net (code "198") (name "unconnected-(U1B-PG0-Pad56)") (class "Default")
      (node (ref "U1") (pin "56") (pinfunction "PG0_56") (pintype "bidirectional"))
    )
    (net (code "199") (name "unconnected-(U1B-PG1-Pad57)") (class "Default")
      (node (ref "U1") (pin "57") (pinfunction "PG1_57") (pintype "bidirectional"))
    )
    (net (code "200") (name "unconnected-(U1B-PG2-Pad87)") (class "Default")
      (node (ref "U1") (pin "87") (pinfunction "PG2_87") (pintype "bidirectional"))
    )
    (net (code "201") (name "unconnected-(U1B-PG3-Pad88)") (class "Default")
      (node (ref "U1") (pin "88") (pinfunction "PG3_88") (pintype "bidirectional"))
    )
    (net (code "202") (name "unconnected-(U1B-PG4-Pad89)") (class "Default")
      (node (ref "U1") (pin "89") (pinfunction "PG4_89") (pintype "bidirectional"))
    )
    (net (code "203") (name "unconnected-(U1B-PG5-Pad90)") (class "Default")
      (node (ref "U1") (pin "90") (pinfunction "PG5_90") (pintype "bidirectional"))
    )
    (net (code "204") (name "unconnected-(U1B-PG6-Pad91)") (class "Default")
      (node (ref "U1") (pin "91") (pinfunction "PG6_91") (pintype "bidirectional"))
    )
    (net (code "205") (name "unconnected-(U1B-PG7-Pad92)") (class "Default")
      (node (ref "U1") (pin "92") (pinfunction "PG7_92") (pintype "bidirectional"))
    )
    (net (code "206") (name "unconnected-(U1B-PG8-Pad93)") (class "Default")
      (node (ref "U1") (pin "93") (pinfunction "PG8_93") (pintype "bidirectional"))
    )
    (net (code "207") (name "unconnected-(U1B-PG9-Pad124)") (class "Default")
      (node (ref "U1") (pin "124") (pinfunction "PG9_124") (pintype "bidirectional"))
    )
    (net (code "208") (name "unconnected-(U1B-PG10-Pad125)") (class "Default")
      (node (ref "U1") (pin "125") (pinfunction "PG10_125") (pintype "bidirectional"))
    )
    (net (code "209") (name "unconnected-(U1B-PG11-Pad126)") (class "Default")
      (node (ref "U1") (pin "126") (pinfunction "PG11_126") (pintype "bidirectional"))
    )
    (net (code "210") (name "unconnected-(U1B-PG12-Pad127)") (class "Default")
      (node (ref "U1") (pin "127") (pinfunction "PG12_127") (pintype "bidirectional"))
    )
    (net (code "211") (name "unconnected-(U1B-PG13-Pad128)") (class "Default")
      (node (ref "U1") (pin "128") (pinfunction "PG13_128") (pintype "bidirectional"))
    )
    (net (code "212") (name "unconnected-(U1B-PG14-Pad129)") (class "Default")
      (node (ref "U1") (pin "129") (pinfunction "PG14_129") (pintype "bidirectional"))
    )
    (net (code "213") (name "unconnected-(U1B-PG15-Pad132)") (class "Default")
      (node (ref "U1") (pin "132") (pinfunction "PG15_132") (pintype "bidirectional"))
    )
    (net (code "214") (name "unconnected-(U1B-PH0-Pad23)") (class "Default")
      (node (ref "U1") (pin "23") (pinfunction "PH0_23") (pintype "bidirectional"))
    )
    (net (code "215") (name "unconnected-(U1B-PH1-Pad24)") (class "Default")
      (node (ref "U1") (pin "24") (pinfunction "PH1_24") (pintype "bidirectional"))
    )
    (net (code "216") (name "unconnected-(U2-NC-Pad9)") (class "Default")
      (node (ref "U2") (pin "9") (pinfunction "NC_9") (pintype "passive+no_connect"))
    )
    (net (code "217") (name "unconnected-(U2-NC-Pad11)") (class "Default")
      (node (ref "U2") (pin "11") (pinfunction "NC_11") (pintype "passive+no_connect"))
    )
    (net (code "218") (name "unconnected-(U2-NC-Pad16)") (class "Default")
      (node (ref "U2") (pin "16") (pinfunction "NC_16") (pintype "passive+no_connect"))
    )
    (net (code "219") (name "unconnected-(U2-NC-Pad24)") (class "Default")
      (node (ref "U2") (pin "24") (pinfunction "NC_24") (pintype "passive+no_connect"))
    )
    (net (code "220") (name "unconnected-(U2-NC-Pad26)") (class "Default")
      (node (ref "U2") (pin "26") (pinfunction "NC_26") (pintype "passive+no_connect"))
    )
    (net (code "221") (name "unconnected-(U2-NC-Pad32)") (class "Default")
      (node (ref "U2") (pin "32") (pinfunction "NC_32") (pintype "passive+no_connect"))
    )
    (net (code "222") (name "unconnected-(U2-POSCMP-Pad30)") (class "Default")
      (node (ref "U2") (pin "30") (pinfunction "POSCMP_30") (pintype "output"))
    )
    (net (code "223") (name "unconnected-(U2-SDOZ_C-Pad12)") (class "Default")
      (node (ref "U2") (pin "12") (pinfunction "SDOZ_C_12") (pintype "output"))
    )
    (net (code "224") (name "unconnected-(U3-EXTINT-Pad13)") (class "Default")
      (node (ref "U3") (pin "13") (pinfunction "EXTINT_13") (pintype "bidirectional"))
    )
    (net (code "225") (name "unconnected-(U3-EXTINT2{slash}GPIO8-Pad5)") (class "Default")
      (node (ref "U3") (pin "5") (pinfunction "EXTINT2/GPIO8_5") (pintype "input"))
    )
    (net (code "226") (name "unconnected-(U3-GPIO2-Pad1)") (class "Default")
      (node (ref "U3") (pin "1") (pinfunction "GPIO2_1") (pintype "bidirectional+no_connect"))
    )
    (net (code "227") (name "unconnected-(U3-GPIO3-Pad12)") (class "Default")
      (node (ref "U3") (pin "12") (pinfunction "GPIO3_12") (pintype "bidirectional+no_connect"))
    )
    (net (code "228") (name "unconnected-(U3-I2C_CLK-Pad15)") (class "Default")
      (node (ref "U3") (pin "15") (pinfunction "I2C_CLK_15") (pintype "input+no_connect"))
    )
    (net (code "229") (name "unconnected-(U3-I2C_DIO-Pad16)") (class "Default")
      (node (ref "U3") (pin "16") (pinfunction "I2C_DIO_16") (pintype "bidirectional+no_connect"))
    )
    (net (code "230") (name "unconnected-(U3-TM_GPIO5-Pad14)") (class "Default")
      (node (ref "U3") (pin "14") (pinfunction "TM_GPIO5_14") (pintype "output"))
    )
    (net (code "231") (name "unconnected-(U3-VANT-Pad9)") (class "Default")
      (node (ref "U3") (pin "9") (pinfunction "VANT_9") (pintype "power_in+no_connect"))
    )
    (net (code "232") (name "unconnected-(U3-VOUT-Pad2)") (class "Default")
      (node (ref "U3") (pin "2") (pinfunction "VOUT_2") (pintype "output+no_connect"))
    )
    (net (code "233") (name "unconnected-(U3-WAKEUP-Pad19)") (class "Default")
      (node (ref "U3") (pin "19") (pinfunction "WAKEUP_19") (pintype "output+no_connect"))
    )
  )
)
